# SCK_URBAN_BOARD_2_3.net
KiCad netlist of a schematic drawn in EAGLE
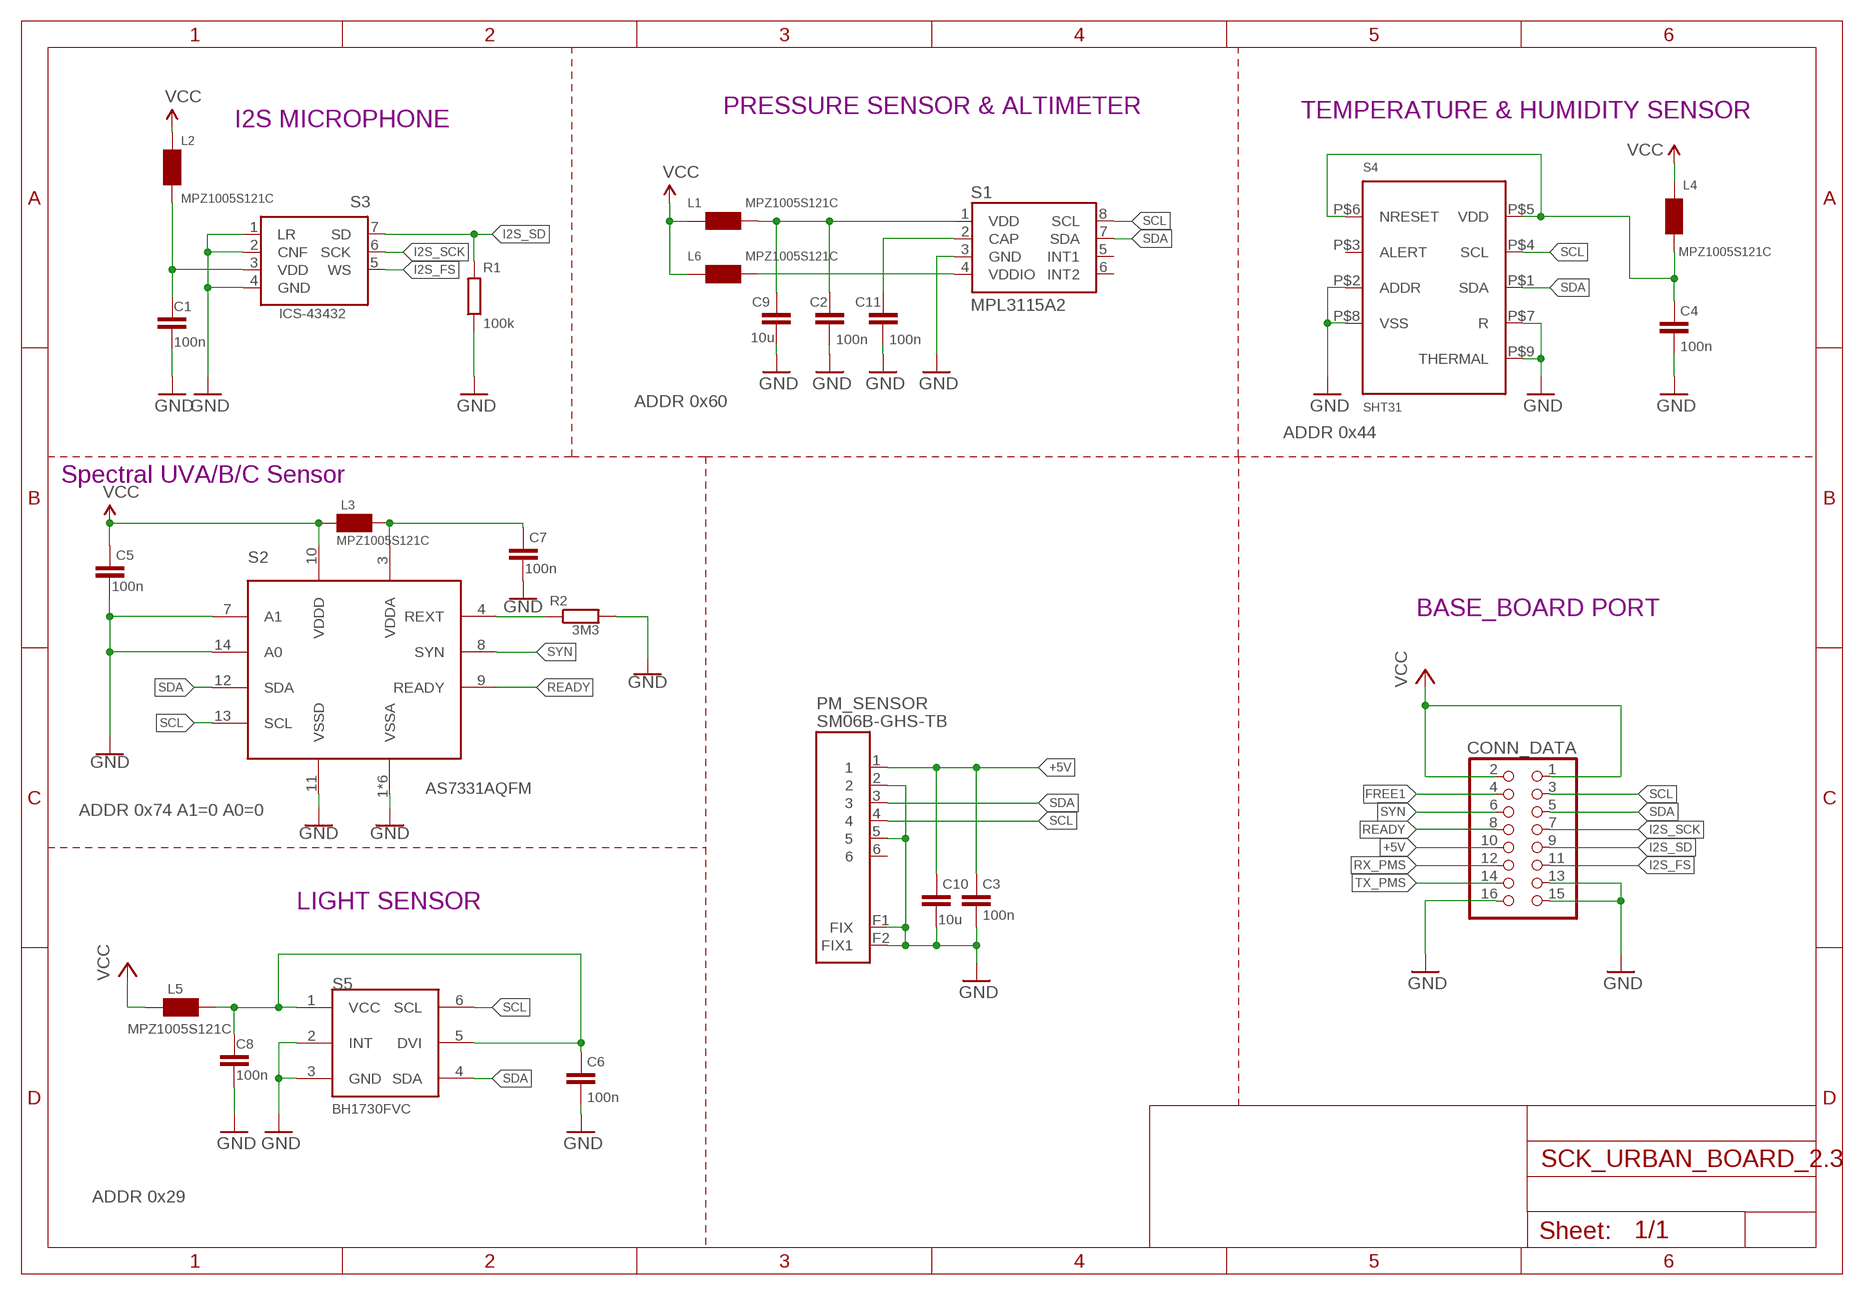
[diagram p0: schematic, sheet 1]

(export (version "E")
  (design (tool "Eeschema 10.0.6"))
  (components
    (comp (ref "C1")
      (value "100n")
      (footprint "eagle-import:C0402")
      (libsource (lib "eagle-import") (part "C-EUC0402"))
    )
    (comp (ref "C2")
      (value "100n")
      (footprint "eagle-import:C0402")
      (libsource (lib "eagle-import") (part "C-EUC0402"))
    )
    (comp (ref "C3")
      (value "100n")
      (footprint "eagle-import:C0402")
      (libsource (lib "eagle-import") (part "C-EUC0402"))
    )
    (comp (ref "C4")
      (value "100n")
      (footprint "eagle-import:C0402")
      (libsource (lib "eagle-import") (part "C-EUC0402"))
    )
    (comp (ref "C5")
      (value "100n")
      (footprint "eagle-import:C0402")
      (libsource (lib "eagle-import") (part "C-EUC0402"))
    )
    (comp (ref "C6")
      (value "100n")
      (footprint "eagle-import:C0402")
      (libsource (lib "eagle-import") (part "C-EUC0402"))
    )
    (comp (ref "C7")
      (value "100n")
      (footprint "eagle-import:C0402")
      (libsource (lib "eagle-import") (part "C-EUC0402"))
    )
    (comp (ref "C8")
      (value "100n")
      (footprint "eagle-import:C0402")
      (libsource (lib "eagle-import") (part "C-EUC0402"))
    )
    (comp (ref "C9")
      (value "10u")
      (footprint "eagle-import:C0603")
      (libsource (lib "eagle-import") (part "C-EUC0603"))
    )
    (comp (ref "C10")
      (value "10u")
      (footprint "eagle-import:C0603")
      (libsource (lib "eagle-import") (part "C-EUC0603"))
    )
    (comp (ref "C11")
      (value "100n")
      (footprint "eagle-import:C0402")
      (libsource (lib "eagle-import") (part "C-EUC0402"))
    )
    (comp (ref "CONN_DATA")
      (value "PINHD_2X8MAL_SMD")
      (footprint "eagle-import:PINHD_2X8_SMD_MALE_UNHOLED")
      (libsource (lib "eagle-import") (part "PINHD_2X8MAL_SMD"))
    )
    (comp (ref "L1")
      (value "MPZ1005S121C")
      (footprint "eagle-import:L0402")
      (libsource (lib "eagle-import") (part "FERRITE-BEAD_0402"))
    )
    (comp (ref "L2")
      (value "MPZ1005S121C")
      (footprint "eagle-import:L0402")
      (libsource (lib "eagle-import") (part "FERRITE-BEAD_0402"))
    )
    (comp (ref "L3")
      (value "MPZ1005S121C")
      (footprint "eagle-import:L0402")
      (libsource (lib "eagle-import") (part "FERRITE-BEAD_0402"))
    )
    (comp (ref "L4")
      (value "MPZ1005S121C")
      (footprint "eagle-import:L0402")
      (libsource (lib "eagle-import") (part "FERRITE-BEAD_0402"))
    )
    (comp (ref "L5")
      (value "MPZ1005S121C")
      (footprint "eagle-import:L0402")
      (libsource (lib "eagle-import") (part "FERRITE-BEAD_0402"))
    )
    (comp (ref "L6")
      (value "MPZ1005S121C")
      (footprint "eagle-import:L0402")
      (libsource (lib "eagle-import") (part "FERRITE-BEAD_0402"))
    )
    (comp (ref "PM_SENSOR")
      (value "SM06B-GHS-TB")
      (footprint "eagle-import:SM06B-GHS-TB")
      (libsource (lib "eagle-import") (part "SM06B-GHS-TB"))
    )
    (comp (ref "R1")
      (value "100k")
      (footprint "eagle-import:R0402")
      (libsource (lib "eagle-import") (part "R-EU_R0402"))
    )
    (comp (ref "R2")
      (value "3M3")
      (footprint "eagle-import:R0402")
      (libsource (lib "eagle-import") (part "R-EU_R0402"))
    )
    (comp (ref "S1")
      (value "MPL3115A2")
      (footprint "eagle-import:MPL3115A2")
      (libsource (lib "eagle-import") (part "MPL3115A2"))
    )
    (comp (ref "S2")
      (value "AS7331AQFM")
      (footprint "eagle-import:OLGA16")
      (libsource (lib "eagle-import") (part "AS7331AQFM"))
    )
    (comp (ref "S3")
      (value "ICS-43432")
      (footprint "eagle-import:ICS-43432")
      (libsource (lib "eagle-import") (part "ICS-43432"))
    )
    (comp (ref "S4")
      (value "SHT31")
      (footprint "eagle-import:DFN8_STH3X-DIS")
      (libsource (lib "eagle-import") (part "SHT3X-DIS"))
    )
    (comp (ref "S5")
      (value "BH1730FVC")
      (footprint "eagle-import:WSOF6")
      (libsource (lib "eagle-import") (part "BH1730FVC"))
    )
  )
  (nets
    (net (code "1") (name "+5V") (class "Default")
      (node (ref "C10") (pin "2") (pinfunction "2_2") (pintype "passive"))
      (node (ref "C3") (pin "2") (pinfunction "2_2") (pintype "passive"))
      (node (ref "CONN_DATA") (pin "10") (pinfunction "10_10") (pintype "passive"))
      (node (ref "PM_SENSOR") (pin "1") (pinfunction "1_1") (pintype "bidirectional"))
    )
    (net (code "2") (name "FREE1") (class "Default")
      (node (ref "CONN_DATA") (pin "4") (pinfunction "4_4") (pintype "passive"))
    )
    (net (code "3") (name "GND") (class "Default")
      (node (ref "C1") (pin "1") (pinfunction "1_1") (pintype "passive"))
      (node (ref "C10") (pin "1") (pinfunction "1_1") (pintype "passive"))
      (node (ref "C11") (pin "1") (pinfunction "1_1") (pintype "passive"))
      (node (ref "C2") (pin "1") (pinfunction "1_1") (pintype "passive"))
      (node (ref "C3") (pin "1") (pinfunction "1_1") (pintype "passive"))
      (node (ref "C4") (pin "1") (pinfunction "1_1") (pintype "passive"))
      (node (ref "C5") (pin "1") (pinfunction "1_1") (pintype "passive"))
      (node (ref "C6") (pin "1") (pinfunction "1_1") (pintype "passive"))
      (node (ref "C7") (pin "1") (pinfunction "1_1") (pintype "passive"))
      (node (ref "C8") (pin "1") (pinfunction "1_1") (pintype "passive"))
      (node (ref "C9") (pin "1") (pinfunction "1_1") (pintype "passive"))
      (node (ref "CONN_DATA") (pin "13") (pinfunction "13_13") (pintype "passive"))
      (node (ref "CONN_DATA") (pin "15") (pinfunction "15_15") (pintype "passive"))
      (node (ref "CONN_DATA") (pin "16") (pinfunction "16_16") (pintype "passive"))
      (node (ref "PM_SENSOR") (pin "2") (pinfunction "2_2") (pintype "bidirectional"))
      (node (ref "PM_SENSOR") (pin "5") (pinfunction "5_5") (pintype "bidirectional"))
      (node (ref "PM_SENSOR") (pin "F1") (pinfunction "FIX_F1") (pintype "bidirectional"))
      (node (ref "PM_SENSOR") (pin "F2") (pinfunction "FIX1_F2") (pintype "bidirectional"))
      (node (ref "R1") (pin "1") (pinfunction "1_1") (pintype "passive"))
      (node (ref "R2") (pin "2") (pinfunction "2_2") (pintype "passive"))
      (node (ref "S1") (pin "3") (pinfunction "GND_3") (pintype "bidirectional"))
      (node (ref "S2") (pin "1") (pinfunction "VSSA_1") (pintype "bidirectional"))
      (node (ref "S2") (pin "11") (pinfunction "VSSD_11") (pintype "bidirectional"))
      (node (ref "S2") (pin "14") (pinfunction "A0_14") (pintype "bidirectional"))
      (node (ref "S2") (pin "15") (pinfunction "VSSA_15") (pintype "bidirectional"))
      (node (ref "S2") (pin "16") (pinfunction "VSSA_16") (pintype "bidirectional"))
      (node (ref "S2") (pin "2") (pinfunction "VSSA_2") (pintype "bidirectional"))
      (node (ref "S2") (pin "5") (pinfunction "VSSA_5") (pintype "bidirectional"))
      (node (ref "S2") (pin "6") (pinfunction "VSSA_6") (pintype "bidirectional"))
      (node (ref "S2") (pin "7") (pinfunction "A1_7") (pintype "bidirectional"))
      (node (ref "S3") (pin "1") (pinfunction "LR_1") (pintype "bidirectional"))
      (node (ref "S3") (pin "2") (pinfunction "CNF_2") (pintype "bidirectional"))
      (node (ref "S3") (pin "4") (pinfunction "GND_4") (pintype "bidirectional"))
      (node (ref "S4") (pin "P$2") (pinfunction "ADDR_P$2") (pintype "bidirectional"))
      (node (ref "S4") (pin "P$7") (pinfunction "R_P$7") (pintype "bidirectional"))
      (node (ref "S4") (pin "P$8") (pinfunction "VSS_P$8") (pintype "bidirectional"))
      (node (ref "S4") (pin "P$9") (pinfunction "THERMAL_P$9") (pintype "bidirectional"))
      (node (ref "S5") (pin "2") (pinfunction "INT_2") (pintype "bidirectional"))
      (node (ref "S5") (pin "3") (pinfunction "GND_3") (pintype "bidirectional"))
    )
    (net (code "4") (name "I2S_FS") (class "Default")
      (node (ref "CONN_DATA") (pin "11") (pinfunction "11_11") (pintype "passive"))
      (node (ref "S3") (pin "5") (pinfunction "WS_5") (pintype "bidirectional"))
    )
    (net (code "5") (name "I2S_SCK") (class "Default")
      (node (ref "CONN_DATA") (pin "7") (pinfunction "7_7") (pintype "passive"))
      (node (ref "S3") (pin "6") (pinfunction "SCK_6") (pintype "bidirectional"))
    )
    (net (code "6") (name "I2S_SD") (class "Default")
      (node (ref "CONN_DATA") (pin "9") (pinfunction "9_9") (pintype "passive"))
      (node (ref "R1") (pin "2") (pinfunction "2_2") (pintype "passive"))
      (node (ref "S3") (pin "7") (pinfunction "SD_7") (pintype "bidirectional"))
    )
    (net (code "7") (name "Net-(S1-CAP)") (class "Default")
      (node (ref "C11") (pin "2") (pinfunction "2_2") (pintype "passive"))
      (node (ref "S1") (pin "2") (pinfunction "CAP_2") (pintype "bidirectional"))
    )
    (net (code "8") (name "Net-(S1-VDD)") (class "Default")
      (node (ref "C2") (pin "2") (pinfunction "2_2") (pintype "passive"))
      (node (ref "C9") (pin "2") (pinfunction "2_2") (pintype "passive"))
      (node (ref "L1") (pin "2") (pinfunction "2_2") (pintype "passive"))
      (node (ref "S1") (pin "1") (pinfunction "VDD_1") (pintype "bidirectional"))
    )
    (net (code "9") (name "Net-(S1-VDDIO)") (class "Default")
      (node (ref "L6") (pin "2") (pinfunction "2_2") (pintype "passive"))
      (node (ref "S1") (pin "4") (pinfunction "VDDIO_4") (pintype "bidirectional"))
    )
    (net (code "10") (name "Net-(S2-REXT)") (class "Default")
      (node (ref "R2") (pin "1") (pinfunction "1_1") (pintype "passive"))
      (node (ref "S2") (pin "4") (pinfunction "REXT_4") (pintype "bidirectional"))
    )
    (net (code "11") (name "Net-(S2-VDDA)") (class "Default")
      (node (ref "C7") (pin "2") (pinfunction "2_2") (pintype "passive"))
      (node (ref "L3") (pin "1") (pinfunction "1_1") (pintype "passive"))
      (node (ref "S2") (pin "3") (pinfunction "VDDA_3") (pintype "bidirectional"))
    )
    (net (code "12") (name "Net-(S3-VDD)") (class "Default")
      (node (ref "C1") (pin "2") (pinfunction "2_2") (pintype "passive"))
      (node (ref "L2") (pin "2") (pinfunction "2_2") (pintype "passive"))
      (node (ref "S3") (pin "3") (pinfunction "VDD_3") (pintype "bidirectional"))
    )
    (net (code "13") (name "Net-(S4-NRESET)") (class "Default")
      (node (ref "C4") (pin "2") (pinfunction "2_2") (pintype "passive"))
      (node (ref "L4") (pin "2") (pinfunction "2_2") (pintype "passive"))
      (node (ref "S4") (pin "P$5") (pinfunction "VDD_P$5") (pintype "bidirectional"))
      (node (ref "S4") (pin "P$6") (pinfunction "NRESET_P$6") (pintype "bidirectional"))
    )
    (net (code "14") (name "Net-(S5-DVI)") (class "Default")
      (node (ref "C6") (pin "2") (pinfunction "2_2") (pintype "passive"))
      (node (ref "C8") (pin "2") (pinfunction "2_2") (pintype "passive"))
      (node (ref "L5") (pin "2") (pinfunction "2_2") (pintype "passive"))
      (node (ref "S5") (pin "1") (pinfunction "VCC_1") (pintype "bidirectional"))
      (node (ref "S5") (pin "5") (pinfunction "DVI_5") (pintype "bidirectional"))
    )
    (net (code "15") (name "READY") (class "Default")
      (node (ref "CONN_DATA") (pin "8") (pinfunction "8_8") (pintype "passive"))
      (node (ref "S2") (pin "9") (pinfunction "READY_9") (pintype "bidirectional"))
    )
    (net (code "16") (name "RX_PMS") (class "Default")
      (node (ref "CONN_DATA") (pin "12") (pinfunction "12_12") (pintype "passive"))
    )
    (net (code "17") (name "SCL") (class "Default")
      (node (ref "CONN_DATA") (pin "3") (pinfunction "3_3") (pintype "passive"))
      (node (ref "PM_SENSOR") (pin "4") (pinfunction "4_4") (pintype "bidirectional"))
      (node (ref "S1") (pin "8") (pinfunction "SCL_8") (pintype "bidirectional"))
      (node (ref "S2") (pin "13") (pinfunction "SCL_13") (pintype "bidirectional"))
      (node (ref "S4") (pin "P$4") (pinfunction "SCL_P$4") (pintype "bidirectional"))
      (node (ref "S5") (pin "6") (pinfunction "SCL_6") (pintype "bidirectional"))
    )
    (net (code "18") (name "SDA") (class "Default")
      (node (ref "CONN_DATA") (pin "5") (pinfunction "5_5") (pintype "passive"))
      (node (ref "PM_SENSOR") (pin "3") (pinfunction "3_3") (pintype "bidirectional"))
      (node (ref "S1") (pin "7") (pinfunction "SDA_7") (pintype "bidirectional"))
      (node (ref "S2") (pin "12") (pinfunction "SDA_12") (pintype "bidirectional"))
      (node (ref "S4") (pin "P$1") (pinfunction "SDA_P$1") (pintype "bidirectional"))
      (node (ref "S5") (pin "4") (pinfunction "SDA_4") (pintype "bidirectional"))
    )
    (net (code "19") (name "SYN") (class "Default")
      (node (ref "CONN_DATA") (pin "6") (pinfunction "6_6") (pintype "passive"))
      (node (ref "S2") (pin "8") (pinfunction "SYN_8") (pintype "bidirectional"))
    )
    (net (code "20") (name "TX_PMS") (class "Default")
      (node (ref "CONN_DATA") (pin "14") (pinfunction "14_14") (pintype "passive"))
    )
    (net (code "21") (name "VCC") (class "Default")
      (node (ref "C5") (pin "2") (pinfunction "2_2") (pintype "passive"))
      (node (ref "CONN_DATA") (pin "1") (pinfunction "1_1") (pintype "passive"))
      (node (ref "CONN_DATA") (pin "2") (pinfunction "2_2") (pintype "passive"))
      (node (ref "L1") (pin "1") (pinfunction "1_1") (pintype "passive"))
      (node (ref "L2") (pin "1") (pinfunction "1_1") (pintype "passive"))
      (node (ref "L3") (pin "2") (pinfunction "2_2") (pintype "passive"))
      (node (ref "L4") (pin "1") (pinfunction "1_1") (pintype "passive"))
      (node (ref "L5") (pin "1") (pinfunction "1_1") (pintype "passive"))
      (node (ref "L6") (pin "1") (pinfunction "1_1") (pintype "passive"))
      (node (ref "S2") (pin "10") (pinfunction "VDDD_10") (pintype "bidirectional"))
    )
    (net (code "22") (name "unconnected-(PM_SENSOR-Pad6)") (class "Default")
      (node (ref "PM_SENSOR") (pin "6") (pinfunction "6_6") (pintype "bidirectional"))
    )
    (net (code "23") (name "unconnected-(S1-INT1-Pad5)") (class "Default")
      (node (ref "S1") (pin "5") (pinfunction "INT1_5") (pintype "bidirectional"))
    )
    (net (code "24") (name "unconnected-(S1-INT2-Pad6)") (class "Default")
      (node (ref "S1") (pin "6") (pinfunction "INT2_6") (pintype "bidirectional"))
    )
    (net (code "25") (name "unconnected-(S4-ALERT-PadP$3)") (class "Default")
      (node (ref "S4") (pin "P$3") (pinfunction "ALERT_P$3") (pintype "bidirectional"))
    )
  )
)
